# dustmap.net
KiCad netlist of a schematic drawn in EAGLE
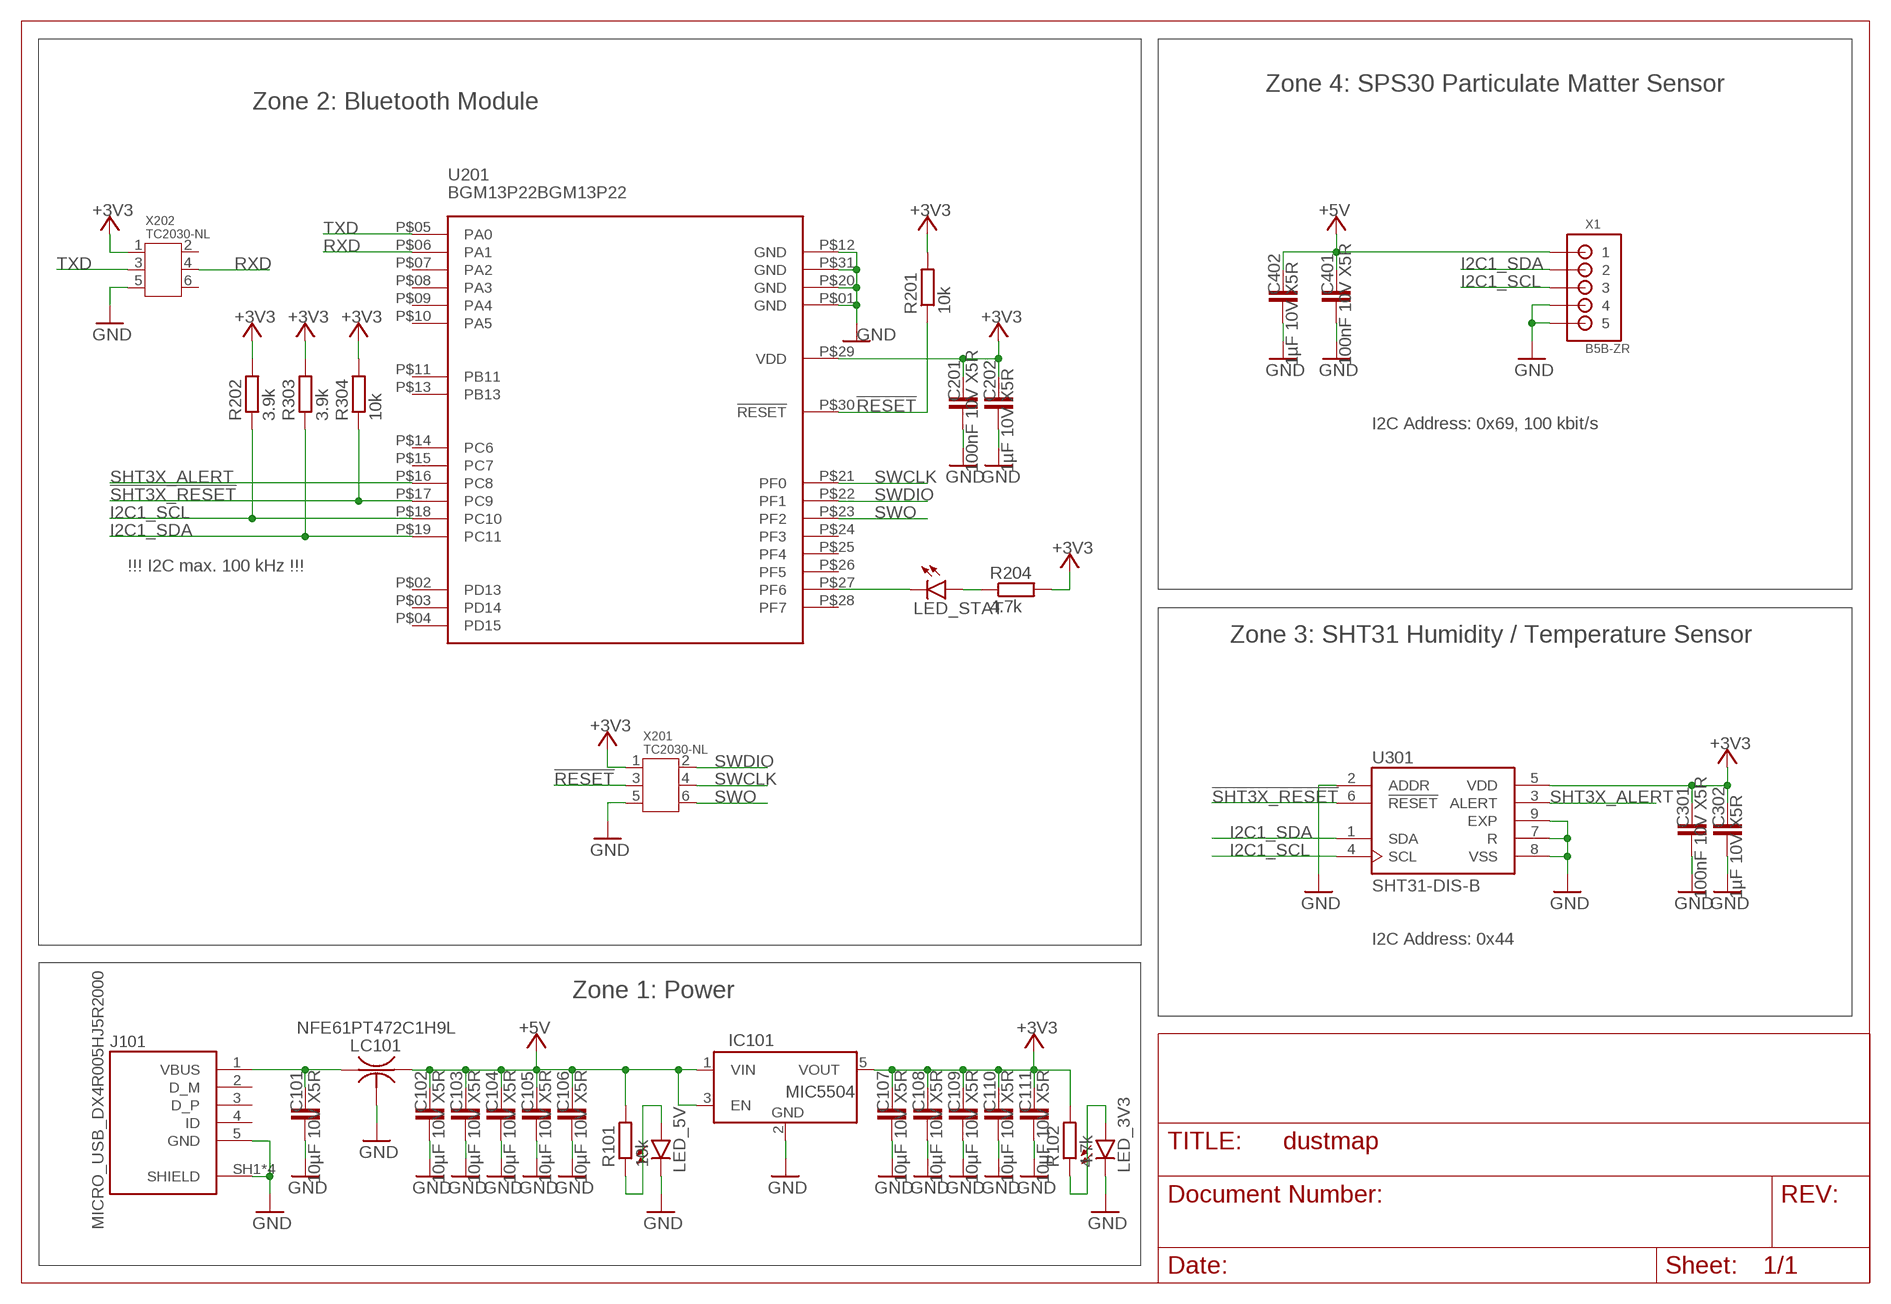
[diagram p0: schematic, sheet 1]

(export (version "E")
  (design (tool "Eeschema 10.0.6"))
  (components
    (comp (ref "C101")
      (value "10µF 10V X5R")
      (footprint "eagle-import:C0603")
      (libsource (lib "eagle-import") (part "C-EUC0603"))
    )
    (comp (ref "C102")
      (value "10µF 10V X5R")
      (footprint "eagle-import:C0603")
      (libsource (lib "eagle-import") (part "C-EUC0603"))
    )
    (comp (ref "C103")
      (value "10µF 10V X5R")
      (footprint "eagle-import:C0603")
      (libsource (lib "eagle-import") (part "C-EUC0603"))
    )
    (comp (ref "C104")
      (value "10µF 10V X5R")
      (footprint "eagle-import:C0603")
      (libsource (lib "eagle-import") (part "C-EUC0603"))
    )
    (comp (ref "C105")
      (value "10µF 10V X5R")
      (footprint "eagle-import:C0603")
      (libsource (lib "eagle-import") (part "C-EUC0603"))
    )
    (comp (ref "C106")
      (value "10µF 10V X5R")
      (footprint "eagle-import:C0603")
      (libsource (lib "eagle-import") (part "C-EUC0603"))
    )
    (comp (ref "C107")
      (value "10µF 10V X5R")
      (footprint "eagle-import:C0603")
      (libsource (lib "eagle-import") (part "C-EUC0603"))
    )
    (comp (ref "C108")
      (value "10µF 10V X5R")
      (footprint "eagle-import:C0603")
      (libsource (lib "eagle-import") (part "C-EUC0603"))
    )
    (comp (ref "C109")
      (value "10µF 10V X5R")
      (footprint "eagle-import:C0603")
      (libsource (lib "eagle-import") (part "C-EUC0603"))
    )
    (comp (ref "C110")
      (value "10µF 10V X5R")
      (footprint "eagle-import:C0603")
      (libsource (lib "eagle-import") (part "C-EUC0603"))
    )
    (comp (ref "C111")
      (value "10µF 10V X5R")
      (footprint "eagle-import:C0603")
      (libsource (lib "eagle-import") (part "C-EUC0603"))
    )
    (comp (ref "C201")
      (value "100nF 10V X5R")
      (footprint "eagle-import:C0603")
      (libsource (lib "eagle-import") (part "C-EUC0603"))
    )
    (comp (ref "C202")
      (value "1µF 10V X5R")
      (footprint "eagle-import:C0603")
      (libsource (lib "eagle-import") (part "C-EUC0603"))
    )
    (comp (ref "C301")
      (value "100nF 10V X5R")
      (footprint "eagle-import:C0603")
      (libsource (lib "eagle-import") (part "C-EUC0603"))
    )
    (comp (ref "C302")
      (value "1µF 10V X5R")
      (footprint "eagle-import:C0603")
      (libsource (lib "eagle-import") (part "C-EUC0603"))
    )
    (comp (ref "C401")
      (value "100nF 10V X5R")
      (footprint "eagle-import:C0603")
      (libsource (lib "eagle-import") (part "C-EUC0603"))
    )
    (comp (ref "C402")
      (value "1µF 10V X5R")
      (footprint "eagle-import:C0603")
      (libsource (lib "eagle-import") (part "C-EUC0603"))
    )
    (comp (ref "IC101")
      (value "MIC5504")
      (footprint "eagle-import:SOT23-5")
      (libsource (lib "eagle-import") (part "MIC5504"))
    )
    (comp (ref "J101")
      (value "MICRO_USB_DX4R005HJ5R2000")
      (footprint "eagle-import:JAE_DX4R005HJ5R2000")
      (fields
        (field (name "DIGI-KEY_PART_NUMBER") "670-2674-1-ND")
        (field (name "MF") "JAE Electronics")
        (field (name "MP") "DX4R005HJ5R2000")
      )
      (libsource (lib "eagle-import") (part "MICRO_USB_DX4R005HJ5R2000"))
    )
    (comp (ref "LC101")
      (value "NFE61PT472C1H9L")
      (footprint "eagle-import:CAP_NFE61P_6P8X1P6")
      (libsource (lib "eagle-import") (part "NFE61PT472C1H9L"))
    )
    (comp (ref "LED_3V3")
      (value "LEDCHIP-LED0603")
      (footprint "eagle-import:CHIP-LED0603")
      (libsource (lib "eagle-import") (part "LEDCHIP-LED0603"))
    )
    (comp (ref "LED_5V")
      (value "LEDCHIP-LED0603")
      (footprint "eagle-import:CHIP-LED0603")
      (libsource (lib "eagle-import") (part "LEDCHIP-LED0603"))
    )
    (comp (ref "LED_STAT")
      (value "LEDCHIP-LED0603")
      (footprint "eagle-import:CHIP-LED0603")
      (libsource (lib "eagle-import") (part "LEDCHIP-LED0603"))
    )
    (comp (ref "R101")
      (value "10k")
      (footprint "eagle-import:R0603")
      (libsource (lib "eagle-import") (part "R-EU_R0603"))
    )
    (comp (ref "R102")
      (value "4.7k")
      (footprint "eagle-import:R0603")
      (libsource (lib "eagle-import") (part "R-EU_R0603"))
    )
    (comp (ref "R201")
      (value "10k")
      (footprint "eagle-import:R0603")
      (libsource (lib "eagle-import") (part "R-EU_R0603"))
    )
    (comp (ref "R202")
      (value "3.9k")
      (footprint "eagle-import:R0603")
      (libsource (lib "eagle-import") (part "R-EU_R0603"))
    )
    (comp (ref "R204")
      (value "4.7k")
      (footprint "eagle-import:R0603")
      (libsource (lib "eagle-import") (part "R-EU_R0603"))
    )
    (comp (ref "R303")
      (value "3.9k")
      (footprint "eagle-import:R0603")
      (libsource (lib "eagle-import") (part "R-EU_R0603"))
    )
    (comp (ref "R304")
      (value "10k")
      (footprint "eagle-import:R0603")
      (libsource (lib "eagle-import") (part "R-EU_R0603"))
    )
    (comp (ref "U201")
      (value "BGM13P22BGM13P22")
      (footprint "eagle-import:BGM13P22")
      (libsource (lib "eagle-import") (part "BGM13P22BGM13P22"))
    )
    (comp (ref "U301")
      (value "SHT31-DIS-B")
      (footprint "eagle-import:SON50P250X250X100-9N")
      (fields (field (name "MF") "Sensirion AG"))
      (libsource (lib "eagle-import") (part "SHT31-DIS-B"))
    )
    (comp (ref "X1")
      (value "B5B-ZR")
      (footprint "eagle-import:B5B-ZR")
      (libsource (lib "eagle-import") (part "B5B-ZR"))
    )
    (comp (ref "X201")
      (value "TC2030-NL")
      (footprint "eagle-import:TC2030-NL")
      (libsource (lib "eagle-import") (part "TC2030-NL"))
    )
    (comp (ref "X202")
      (value "TC2030-NL")
      (footprint "eagle-import:TC2030-NL")
      (libsource (lib "eagle-import") (part "TC2030-NL"))
    )
  )
  (nets
    (net (code "1") (name "+3V3") (class "Default")
      (node (ref "C107") (pin "1") (pinfunction "1_1") (pintype "passive"))
      (node (ref "C108") (pin "1") (pinfunction "1_1") (pintype "passive"))
      (node (ref "C109") (pin "1") (pinfunction "1_1") (pintype "passive"))
      (node (ref "C110") (pin "1") (pinfunction "1_1") (pintype "passive"))
      (node (ref "C111") (pin "1") (pinfunction "1_1") (pintype "passive"))
      (node (ref "C201") (pin "1") (pinfunction "1_1") (pintype "passive"))
      (node (ref "C202") (pin "1") (pinfunction "1_1") (pintype "passive"))
      (node (ref "C301") (pin "1") (pinfunction "1_1") (pintype "passive"))
      (node (ref "C302") (pin "1") (pinfunction "1_1") (pintype "passive"))
      (node (ref "IC101") (pin "5") (pinfunction "VOUT_5") (pintype "output"))
      (node (ref "R102") (pin "2") (pinfunction "2_2") (pintype "passive"))
      (node (ref "R201") (pin "2") (pinfunction "2_2") (pintype "passive"))
      (node (ref "R202") (pin "2") (pinfunction "2_2") (pintype "passive"))
      (node (ref "R204") (pin "2") (pinfunction "2_2") (pintype "passive"))
      (node (ref "R303") (pin "2") (pinfunction "2_2") (pintype "passive"))
      (node (ref "R304") (pin "2") (pinfunction "2_2") (pintype "passive"))
      (node (ref "U201") (pin "P$29") (pinfunction "VDD_P$29") (pintype "power_in"))
      (node (ref "U301") (pin "5") (pinfunction "VDD_5") (pintype "power_in"))
      (node (ref "X201") (pin "1") (pinfunction "1_1") (pintype "passive"))
      (node (ref "X202") (pin "1") (pinfunction "1_1") (pintype "passive"))
    )
    (net (code "2") (name "+5V") (class "Default")
      (node (ref "C102") (pin "1") (pinfunction "1_1") (pintype "passive"))
      (node (ref "C103") (pin "1") (pinfunction "1_1") (pintype "passive"))
      (node (ref "C104") (pin "1") (pinfunction "1_1") (pintype "passive"))
      (node (ref "C105") (pin "1") (pinfunction "1_1") (pintype "passive"))
      (node (ref "C106") (pin "1") (pinfunction "1_1") (pintype "passive"))
      (node (ref "C401") (pin "1") (pinfunction "1_1") (pintype "passive"))
      (node (ref "C402") (pin "1") (pinfunction "1_1") (pintype "passive"))
      (node (ref "IC101") (pin "1") (pinfunction "VIN_1") (pintype "passive"))
      (node (ref "IC101") (pin "3") (pinfunction "EN_3") (pintype "passive"))
      (node (ref "LC101") (pin "3") (pinfunction "3_3") (pintype "passive"))
      (node (ref "R101") (pin "2") (pinfunction "2_2") (pintype "passive"))
      (node (ref "X1") (pin "1") (pinfunction "1_1") (pintype "bidirectional"))
    )
    (net (code "3") (name "/I2C1_SCL") (class "Default")
      (node (ref "R202") (pin "1") (pinfunction "1_1") (pintype "passive"))
      (node (ref "U201") (pin "P$18") (pinfunction "PC10_P$18") (pintype "bidirectional"))
      (node (ref "U301") (pin "4") (pinfunction "SCL_4") (pintype "bidirectional"))
      (node (ref "X1") (pin "3") (pinfunction "3_3") (pintype "bidirectional"))
    )
    (net (code "4") (name "/I2C1_SDA") (class "Default")
      (node (ref "R303") (pin "1") (pinfunction "1_1") (pintype "passive"))
      (node (ref "U201") (pin "P$19") (pinfunction "PC11_P$19") (pintype "bidirectional"))
      (node (ref "U301") (pin "1") (pinfunction "SDA_1") (pintype "bidirectional"))
      (node (ref "X1") (pin "2") (pinfunction "2_2") (pintype "bidirectional"))
    )
    (net (code "5") (name "/RXD") (class "Default")
      (node (ref "U201") (pin "P$06") (pinfunction "PA1_P$06") (pintype "bidirectional"))
      (node (ref "X202") (pin "4") (pinfunction "4_4") (pintype "passive"))
    )
    (net (code "6") (name "/SHT3X_ALERT") (class "Default")
      (node (ref "U201") (pin "P$16") (pinfunction "PC8_P$16") (pintype "bidirectional"))
      (node (ref "U301") (pin "3") (pinfunction "ALERT_3") (pintype "output"))
    )
    (net (code "7") (name "/SWCLK") (class "Default")
      (node (ref "U201") (pin "P$21") (pinfunction "PF0_P$21") (pintype "bidirectional"))
      (node (ref "X201") (pin "4") (pinfunction "4_4") (pintype "passive"))
    )
    (net (code "8") (name "/SWDIO") (class "Default")
      (node (ref "U201") (pin "P$22") (pinfunction "PF1_P$22") (pintype "bidirectional"))
      (node (ref "X201") (pin "2") (pinfunction "2_2") (pintype "passive"))
    )
    (net (code "9") (name "/SWO") (class "Default")
      (node (ref "U201") (pin "P$23") (pinfunction "PF2_P$23") (pintype "bidirectional"))
      (node (ref "X201") (pin "6") (pinfunction "6_6") (pintype "passive"))
    )
    (net (code "10") (name "/TXD") (class "Default")
      (node (ref "U201") (pin "P$05") (pinfunction "PA0_P$05") (pintype "bidirectional"))
      (node (ref "X202") (pin "3") (pinfunction "3_3") (pintype "passive"))
    )
    (net (code "11") (name "/~{RESET}") (class "Default")
      (node (ref "R201") (pin "1") (pinfunction "1_1") (pintype "passive"))
      (node (ref "U201") (pin "P$30") (pinfunction "~{RESET}_P$30") (pintype "input"))
      (node (ref "X201") (pin "3") (pinfunction "3_3") (pintype "passive"))
    )
    (net (code "12") (name "/~{SHT3X_RESET}") (class "Default")
      (node (ref "R304") (pin "1") (pinfunction "1_1") (pintype "passive"))
      (node (ref "U201") (pin "P$17") (pinfunction "PC9_P$17") (pintype "bidirectional"))
      (node (ref "U301") (pin "6") (pinfunction "~{RESET}_6") (pintype "input"))
    )
    (net (code "13") (name "GND") (class "Default")
      (node (ref "C101") (pin "2") (pinfunction "2_2") (pintype "passive"))
      (node (ref "C102") (pin "2") (pinfunction "2_2") (pintype "passive"))
      (node (ref "C103") (pin "2") (pinfunction "2_2") (pintype "passive"))
      (node (ref "C104") (pin "2") (pinfunction "2_2") (pintype "passive"))
      (node (ref "C105") (pin "2") (pinfunction "2_2") (pintype "passive"))
      (node (ref "C106") (pin "2") (pinfunction "2_2") (pintype "passive"))
      (node (ref "C107") (pin "2") (pinfunction "2_2") (pintype "passive"))
      (node (ref "C108") (pin "2") (pinfunction "2_2") (pintype "passive"))
      (node (ref "C109") (pin "2") (pinfunction "2_2") (pintype "passive"))
      (node (ref "C110") (pin "2") (pinfunction "2_2") (pintype "passive"))
      (node (ref "C111") (pin "2") (pinfunction "2_2") (pintype "passive"))
      (node (ref "C201") (pin "2") (pinfunction "2_2") (pintype "passive"))
      (node (ref "C202") (pin "2") (pinfunction "2_2") (pintype "passive"))
      (node (ref "C301") (pin "2") (pinfunction "2_2") (pintype "passive"))
      (node (ref "C302") (pin "2") (pinfunction "2_2") (pintype "passive"))
      (node (ref "C401") (pin "2") (pinfunction "2_2") (pintype "passive"))
      (node (ref "C402") (pin "2") (pinfunction "2_2") (pintype "passive"))
      (node (ref "IC101") (pin "2") (pinfunction "GND_2") (pintype "power_in"))
      (node (ref "J101") (pin "5") (pinfunction "GND_5") (pintype "passive"))
      (node (ref "J101") (pin "SH1") (pinfunction "SHIELD_SH1") (pintype "passive"))
      (node (ref "J101") (pin "SH2") (pinfunction "SHIELD_SH2") (pintype "passive"))
      (node (ref "J101") (pin "SH3") (pinfunction "SHIELD_SH3") (pintype "passive"))
      (node (ref "J101") (pin "SH4") (pinfunction "SHIELD_SH4") (pintype "passive"))
      (node (ref "LC101") (pin "2") (pinfunction "2_2") (pintype "passive"))
      (node (ref "LED_3V3") (pin "C") (pinfunction "C_C") (pintype "passive"))
      (node (ref "LED_5V") (pin "C") (pinfunction "C_C") (pintype "passive"))
      (node (ref "U201") (pin "P$01") (pinfunction "GND_P$01") (pintype "power_in"))
      (node (ref "U201") (pin "P$12") (pinfunction "GND_P$12") (pintype "power_in"))
      (node (ref "U201") (pin "P$20") (pinfunction "GND_P$20") (pintype "power_in"))
      (node (ref "U201") (pin "P$31") (pinfunction "GND_P$31") (pintype "power_in"))
      (node (ref "U301") (pin "2") (pinfunction "ADDR_2") (pintype "input"))
      (node (ref "U301") (pin "7") (pinfunction "R_7") (pintype "power_in"))
      (node (ref "U301") (pin "8") (pinfunction "VSS_8") (pintype "power_in"))
      (node (ref "U301") (pin "9") (pinfunction "EXP_9") (pintype "power_in"))
      (node (ref "X1") (pin "4") (pinfunction "4_4") (pintype "bidirectional"))
      (node (ref "X1") (pin "5") (pinfunction "5_5") (pintype "bidirectional"))
      (node (ref "X201") (pin "5") (pinfunction "5_5") (pintype "passive"))
      (node (ref "X202") (pin "5") (pinfunction "5_5") (pintype "passive"))
    )
    (net (code "14") (name "Net-(J101-VBUS)") (class "Default")
      (node (ref "C101") (pin "1") (pinfunction "1_1") (pintype "passive"))
      (node (ref "J101") (pin "1") (pinfunction "VBUS_1") (pintype "passive"))
      (node (ref "LC101") (pin "1") (pinfunction "1_1") (pintype "passive"))
    )
    (net (code "15") (name "Net-(LED_3V3-PadA)") (class "Default")
      (node (ref "LED_3V3") (pin "A") (pinfunction "A_A") (pintype "passive"))
      (node (ref "R102") (pin "1") (pinfunction "1_1") (pintype "passive"))
    )
    (net (code "16") (name "Net-(LED_5V-PadA)") (class "Default")
      (node (ref "LED_5V") (pin "A") (pinfunction "A_A") (pintype "passive"))
      (node (ref "R101") (pin "1") (pinfunction "1_1") (pintype "passive"))
    )
    (net (code "17") (name "Net-(LED_STAT-PadA)") (class "Default")
      (node (ref "LED_STAT") (pin "A") (pinfunction "A_A") (pintype "passive"))
      (node (ref "R204") (pin "1") (pinfunction "1_1") (pintype "passive"))
    )
    (net (code "18") (name "Net-(U201-PF6)") (class "Default")
      (node (ref "LED_STAT") (pin "C") (pinfunction "C_C") (pintype "passive"))
      (node (ref "U201") (pin "P$27") (pinfunction "PF6_P$27") (pintype "bidirectional"))
    )
    (net (code "19") (name "unconnected-(J101-D_M-Pad2)") (class "Default")
      (node (ref "J101") (pin "2") (pinfunction "D_M_2") (pintype "passive"))
    )
    (net (code "20") (name "unconnected-(J101-D_P-Pad3)") (class "Default")
      (node (ref "J101") (pin "3") (pinfunction "D_P_3") (pintype "passive"))
    )
    (net (code "21") (name "unconnected-(J101-ID-Pad4)") (class "Default")
      (node (ref "J101") (pin "4") (pinfunction "ID_4") (pintype "passive"))
    )
    (net (code "22") (name "unconnected-(U201-PA2-PadP$07)") (class "Default")
      (node (ref "U201") (pin "P$07") (pinfunction "PA2_P$07") (pintype "bidirectional"))
    )
    (net (code "23") (name "unconnected-(U201-PA3-PadP$08)") (class "Default")
      (node (ref "U201") (pin "P$08") (pinfunction "PA3_P$08") (pintype "bidirectional"))
    )
    (net (code "24") (name "unconnected-(U201-PA4-PadP$09)") (class "Default")
      (node (ref "U201") (pin "P$09") (pinfunction "PA4_P$09") (pintype "bidirectional"))
    )
    (net (code "25") (name "unconnected-(U201-PA5-PadP$10)") (class "Default")
      (node (ref "U201") (pin "P$10") (pinfunction "PA5_P$10") (pintype "bidirectional"))
    )
    (net (code "26") (name "unconnected-(U201-PB11-PadP$11)") (class "Default")
      (node (ref "U201") (pin "P$11") (pinfunction "PB11_P$11") (pintype "bidirectional"))
    )
    (net (code "27") (name "unconnected-(U201-PB13-PadP$13)") (class "Default")
      (node (ref "U201") (pin "P$13") (pinfunction "PB13_P$13") (pintype "bidirectional"))
    )
    (net (code "28") (name "unconnected-(U201-PC6-PadP$14)") (class "Default")
      (node (ref "U201") (pin "P$14") (pinfunction "PC6_P$14") (pintype "bidirectional"))
    )
    (net (code "29") (name "unconnected-(U201-PC7-PadP$15)") (class "Default")
      (node (ref "U201") (pin "P$15") (pinfunction "PC7_P$15") (pintype "bidirectional"))
    )
    (net (code "30") (name "unconnected-(U201-PD13-PadP$02)") (class "Default")
      (node (ref "U201") (pin "P$02") (pinfunction "PD13_P$02") (pintype "bidirectional"))
    )
    (net (code "31") (name "unconnected-(U201-PD14-PadP$03)") (class "Default")
      (node (ref "U201") (pin "P$03") (pinfunction "PD14_P$03") (pintype "bidirectional"))
    )
    (net (code "32") (name "unconnected-(U201-PD15-PadP$04)") (class "Default")
      (node (ref "U201") (pin "P$04") (pinfunction "PD15_P$04") (pintype "bidirectional"))
    )
    (net (code "33") (name "unconnected-(U201-PF3-PadP$24)") (class "Default")
      (node (ref "U201") (pin "P$24") (pinfunction "PF3_P$24") (pintype "bidirectional"))
    )
    (net (code "34") (name "unconnected-(U201-PF4-PadP$25)") (class "Default")
      (node (ref "U201") (pin "P$25") (pinfunction "PF4_P$25") (pintype "bidirectional"))
    )
    (net (code "35") (name "unconnected-(U201-PF5-PadP$26)") (class "Default")
      (node (ref "U201") (pin "P$26") (pinfunction "PF5_P$26") (pintype "bidirectional"))
    )
    (net (code "36") (name "unconnected-(U201-PF7-PadP$28)") (class "Default")
      (node (ref "U201") (pin "P$28") (pinfunction "PF7_P$28") (pintype "bidirectional"))
    )
    (net (code "37") (name "unconnected-(X202-Pad2)") (class "Default")
      (node (ref "X202") (pin "2") (pinfunction "2_2") (pintype "passive"))
    )
    (net (code "38") (name "unconnected-(X202-Pad6)") (class "Default")
      (node (ref "X202") (pin "6") (pinfunction "6_6") (pintype "passive"))
    )
  )
)
